# CPU.net
KiCad netlist of a schematic drawn in Altium Designer
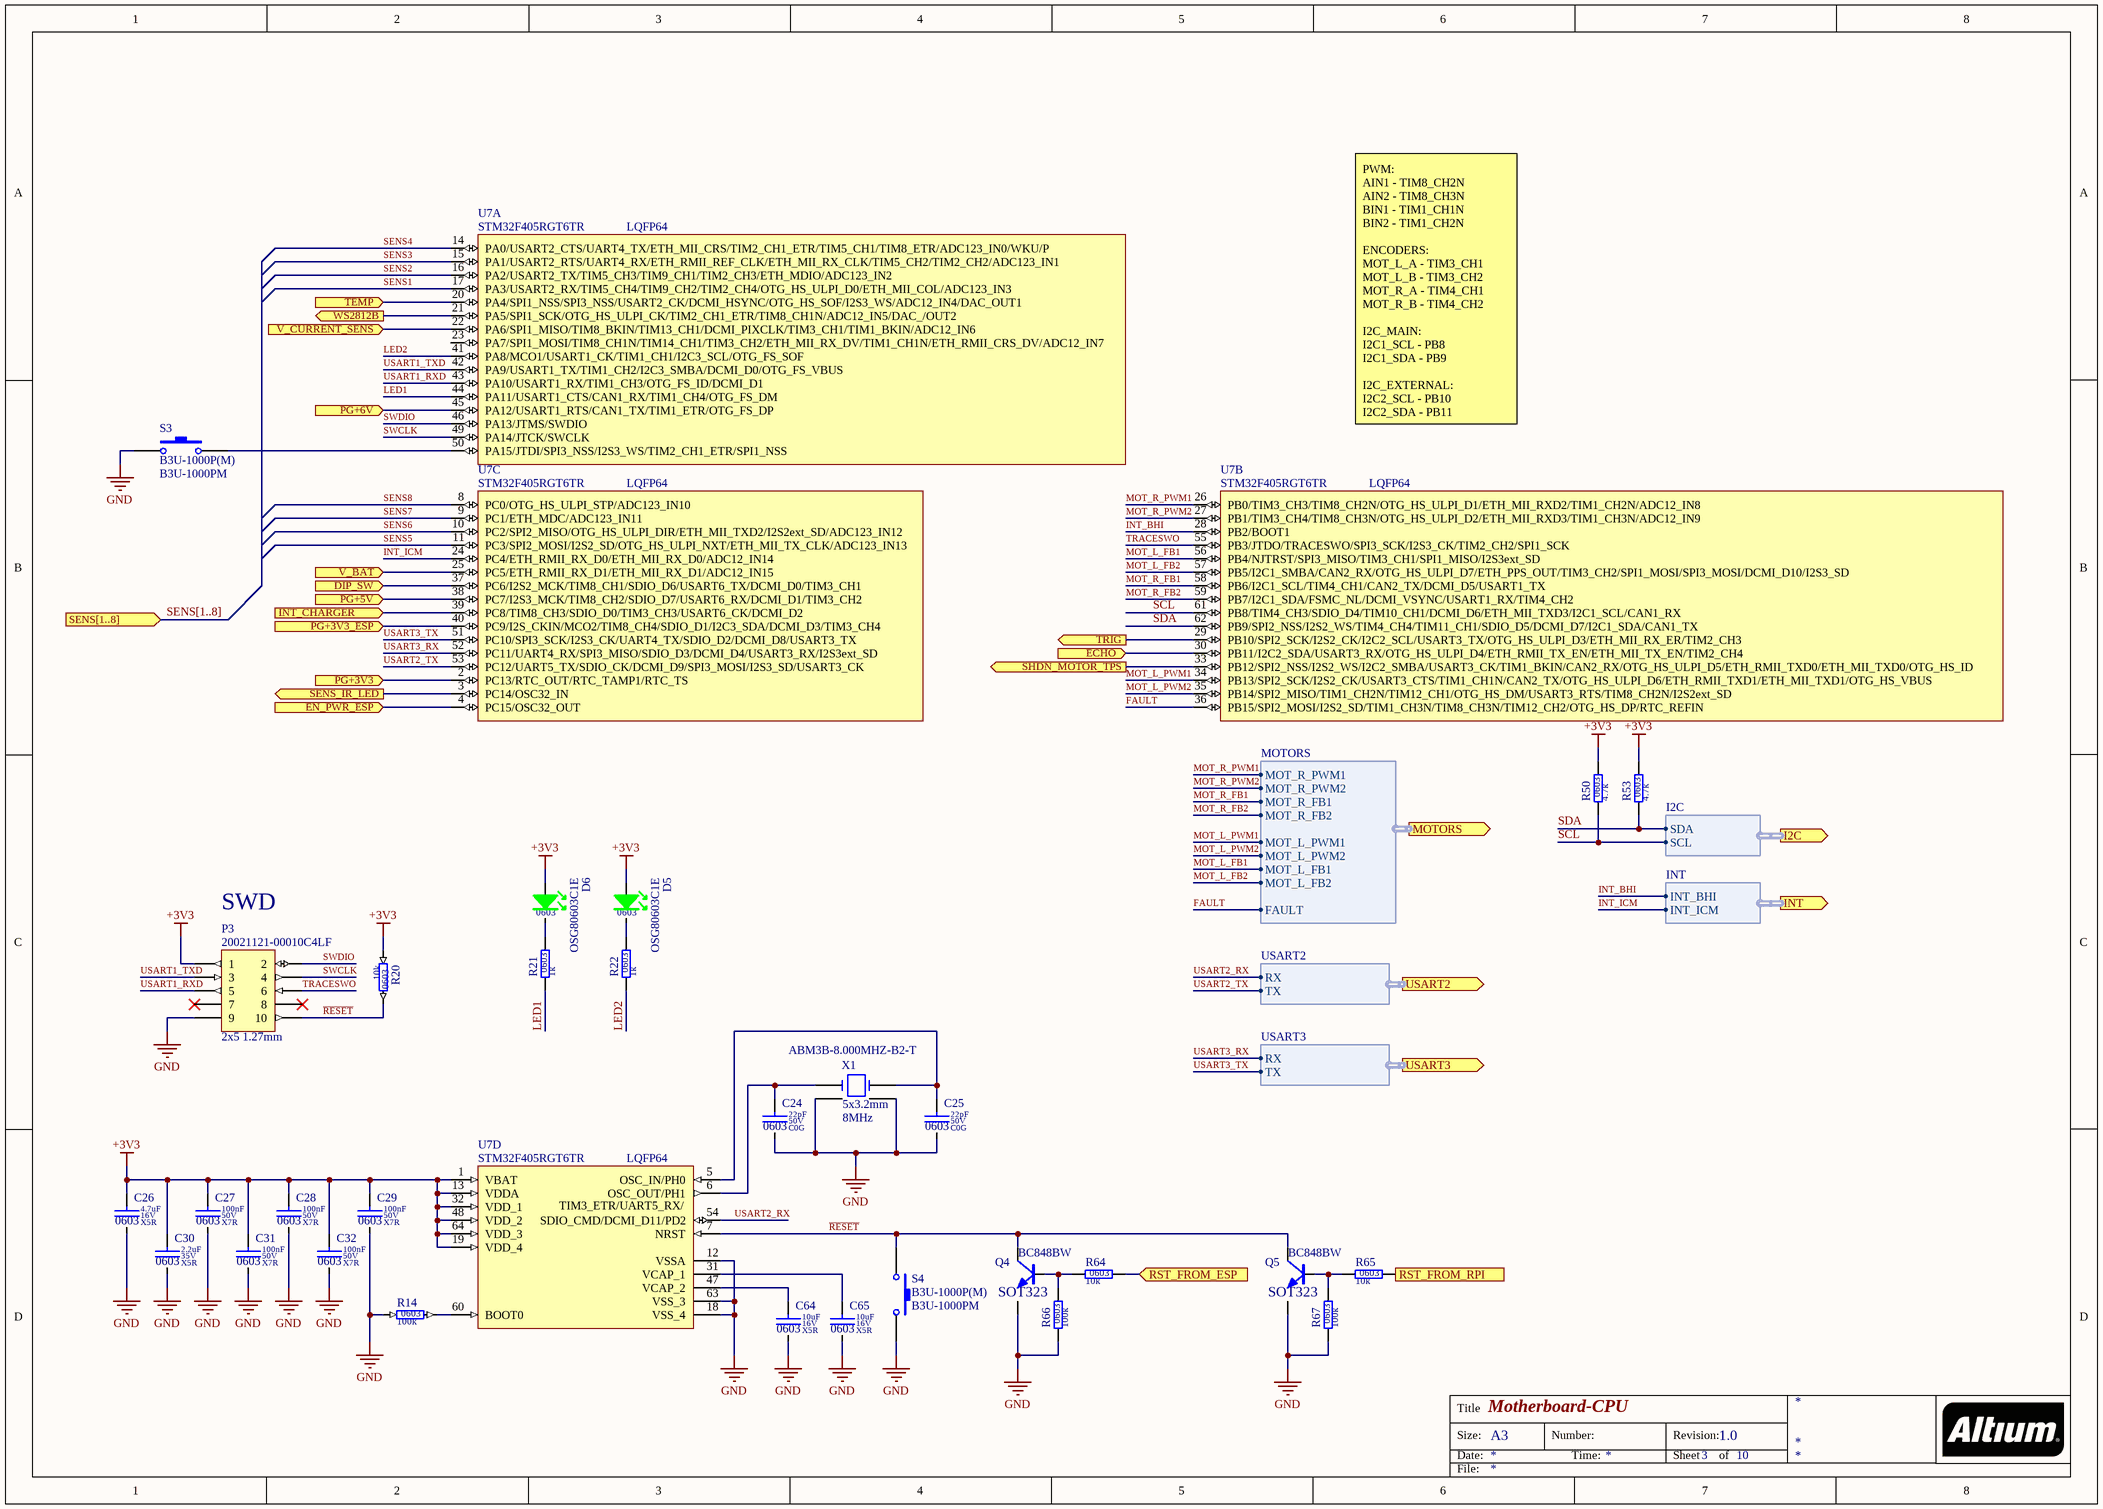
[diagram p0: CPU.SchDoc]

(export (version "E")
  (design (tool "Eeschema 10.0.6"))
  (components
    (comp (ref "C24")
      (value "22pF")
      (footprint "C_0603_1608")
      (description "Capacitor")
      (fields
        (field (name "DIELECTRIC") "C0G")
        (field (name "VOLTAGE") "50V")
        (field (name "SCH_FOOTPRINT") "0603")
        (field (name "PART NUMBER") "C_22pF_50V_C0G_0603_5")
        (field (name "MANUFACTURER") "Yageo")
      )
      (libsource (lib "Library") (part "C"))
    )
    (comp (ref "C25")
      (value "22pF")
      (footprint "C_0603_1608")
      (description "Capacitor")
      (fields
        (field (name "DIELECTRIC") "C0G")
        (field (name "VOLTAGE") "50V")
        (field (name "SCH_FOOTPRINT") "0603")
        (field (name "PART NUMBER") "C_22pF_50V_C0G_0603_5")
        (field (name "MANUFACTURER") "Yageo")
      )
      (libsource (lib "Library") (part "C"))
    )
    (comp (ref "C26")
      (value "4.7uF")
      (footprint "C_0603_1608")
      (description "Capacitor")
      (fields
        (field (name "DIELECTRIC") "X5R")
        (field (name "VOLTAGE") "16V")
        (field (name "SCH_FOOTPRINT") "0603")
        (field (name "PART NUMBER") "C_4.7uF_16V_X5R_0603_10")
        (field (name "MANUFACTURER") "Murata")
      )
      (libsource (lib "Library") (part "C"))
    )
    (comp (ref "C27")
      (value "100nF")
      (footprint "C_0603_1608")
      (description "Capacitor")
      (fields
        (field (name "DIELECTRIC") "X7R")
        (field (name "VOLTAGE") "50V")
        (field (name "SCH_FOOTPRINT") "0603")
        (field (name "PART NUMBER") "C_100nF_50V_X7R_0603_5")
        (field (name "MANUFACTURER") "Samsung")
      )
      (libsource (lib "Library") (part "C"))
    )
    (comp (ref "C28")
      (value "100nF")
      (footprint "C_0603_1608")
      (description "Capacitor")
      (fields
        (field (name "DIELECTRIC") "X7R")
        (field (name "VOLTAGE") "50V")
        (field (name "SCH_FOOTPRINT") "0603")
        (field (name "PART NUMBER") "C_100nF_50V_X7R_0603_5")
        (field (name "MANUFACTURER") "Samsung")
      )
      (libsource (lib "Library") (part "C"))
    )
    (comp (ref "C29")
      (value "100nF")
      (footprint "C_0603_1608")
      (description "Capacitor")
      (fields
        (field (name "DIELECTRIC") "X7R")
        (field (name "VOLTAGE") "50V")
        (field (name "SCH_FOOTPRINT") "0603")
        (field (name "PART NUMBER") "C_100nF_50V_X7R_0603_5")
        (field (name "MANUFACTURER") "Samsung")
      )
      (libsource (lib "Library") (part "C"))
    )
    (comp (ref "C30")
      (value "2.2uF")
      (footprint "C_0603_1608")
      (description "Capacitor")
      (fields
        (field (name "DIELECTRIC") "X5R")
        (field (name "VOLTAGE") "35V")
        (field (name "SCH_FOOTPRINT") "0603")
        (field (name "PART NUMBER") "C_2.2uF_35V_X5R_0603_10")
        (field (name "MANUFACTURER") "Murata")
      )
      (libsource (lib "Library") (part "C"))
    )
    (comp (ref "C31")
      (value "100nF")
      (footprint "C_0603_1608")
      (description "Capacitor")
      (fields
        (field (name "DIELECTRIC") "X7R")
        (field (name "VOLTAGE") "50V")
        (field (name "SCH_FOOTPRINT") "0603")
        (field (name "PART NUMBER") "C_100nF_50V_X7R_0603_5")
        (field (name "MANUFACTURER") "Samsung")
      )
      (libsource (lib "Library") (part "C"))
    )
    (comp (ref "C32")
      (value "100nF")
      (footprint "C_0603_1608")
      (description "Capacitor")
      (fields
        (field (name "DIELECTRIC") "X7R")
        (field (name "VOLTAGE") "50V")
        (field (name "SCH_FOOTPRINT") "0603")
        (field (name "PART NUMBER") "C_100nF_50V_X7R_0603_5")
        (field (name "MANUFACTURER") "Samsung")
      )
      (libsource (lib "Library") (part "C"))
    )
    (comp (ref "C64")
      (value "10uF")
      (footprint "C_0603_1608")
      (description "Capacitor")
      (fields
        (field (name "DIELECTRIC") "X5R")
        (field (name "VOLTAGE") "16V")
        (field (name "SCH_FOOTPRINT") "0603")
        (field (name "PART NUMBER") "C_10uF_16V_X5R_0603_20")
        (field (name "MANUFACTURER") "Samsung Electro-Mechanics")
      )
      (libsource (lib "Library") (part "C"))
    )
    (comp (ref "C65")
      (value "10uF")
      (footprint "C_0603_1608")
      (description "Capacitor")
      (fields
        (field (name "DIELECTRIC") "X5R")
        (field (name "VOLTAGE") "16V")
        (field (name "SCH_FOOTPRINT") "0603")
        (field (name "PART NUMBER") "C_10uF_16V_X5R_0603_20")
        (field (name "MANUFACTURER") "Samsung Electro-Mechanics")
      )
      (libsource (lib "Library") (part "C"))
    )
    (comp (ref "D5")
      (value "OSG80603C1E")
      (footprint "OL_0603_1608")
      (description "LED GREEN")
      (fields
        (field (name "SCH_FOOTPRINT") "0603")
        (field (name "PART NUMBER") "OL_G_0603_OSG80603C1E")
        (field (name "MANUFACTURER") "Optosupply")
      )
      (libsource (lib "Library") (part "OL_G"))
    )
    (comp (ref "D6")
      (value "OSG80603C1E")
      (footprint "OL_0603_1608")
      (description "LED GREEN")
      (fields
        (field (name "SCH_FOOTPRINT") "0603")
        (field (name "PART NUMBER") "OL_G_0603_OSG80603C1E")
        (field (name "MANUFACTURER") "Optosupply")
      )
      (libsource (lib "Library") (part "OL_G"))
    )
    (comp (ref "P3")
      (value "20021121-00010C4LF")
      (footprint "P_HEADER_2x5_1.27")
      (description "Pin Header")
      (fields
        (field (name "PART NUMBER") "P_HEADER_2x5_1.27")
        (field (name "SCH_FOOTPRINT") "2x5 1.27mm")
        (field (name "MANUFACTURER") "FCI")
      )
      (libsource (lib "Library") (part "P_HEADER_2x5"))
    )
    (comp (ref "Q4")
      (value "BC848BW")
      (footprint "SOT323_SC70")
      (fields
        (field (name "PART NUMBER") "QNP_BC848BW_30V_0A1")
        (field (name "SCH_FOOTPRINT") "SOT323")
        (field (name "VOLTAGE") "30V")
        (field (name "MANUFACTURER") "Diotec Semiconductor")
      )
      (libsource (lib "Library") (part "QNP_BEC"))
    )
    (comp (ref "Q5")
      (value "BC848BW")
      (footprint "SOT323_SC70")
      (fields
        (field (name "PART NUMBER") "QNP_BC848BW_30V_0A1")
        (field (name "SCH_FOOTPRINT") "SOT323")
        (field (name "VOLTAGE") "30V")
        (field (name "MANUFACTURER") "Diotec Semiconductor")
      )
      (libsource (lib "Library") (part "QNP_BEC"))
    )
    (comp (ref "R14")
      (value "100k")
      (footprint "R_0603_1608")
      (fields
        (field (name "SCH_FOOTPRINT") "0603")
        (field (name "PART NUMBER") "R_100k_0603_1")
        (field (name "VOLTAGE") "50V")
        (field (name "POWER") "100mW")
      )
      (libsource (lib "") (part "R_1"))
    )
    (comp (ref "R20")
      (value "10k")
      (footprint "R_0603_1608")
      (fields
        (field (name "SCH_FOOTPRINT") "0603")
        (field (name "PART NUMBER") "R_10k_0603_1")
        (field (name "VOLTAGE") "75V")
        (field (name "POWER") "100mW")
      )
      (libsource (lib "") (part "R_1"))
    )
    (comp (ref "R21")
      (value "1k")
      (footprint "R_0603_1608")
      (fields
        (field (name "SCH_FOOTPRINT") "0603")
        (field (name "PART NUMBER") "R_1k_0603_1")
        (field (name "VOLTAGE") "75V")
        (field (name "POWER") "100mW")
      )
      (libsource (lib "Library") (part "R"))
    )
    (comp (ref "R22")
      (value "1k")
      (footprint "R_0603_1608")
      (fields
        (field (name "SCH_FOOTPRINT") "0603")
        (field (name "PART NUMBER") "R_1k_0603_1")
        (field (name "VOLTAGE") "75V")
        (field (name "POWER") "100mW")
      )
      (libsource (lib "Library") (part "R"))
    )
    (comp (ref "R50")
      (value "4.7k")
      (footprint "R_0603_1608")
      (fields
        (field (name "SCH_FOOTPRINT") "0603")
        (field (name "PART NUMBER") "R_4.7k_0603_1")
        (field (name "VOLTAGE") "75V")
        (field (name "POWER") "100mW")
      )
      (libsource (lib "Library") (part "R"))
    )
    (comp (ref "R53")
      (value "4.7k")
      (footprint "R_0603_1608")
      (fields
        (field (name "SCH_FOOTPRINT") "0603")
        (field (name "PART NUMBER") "R_4.7k_0603_1")
        (field (name "VOLTAGE") "75V")
        (field (name "POWER") "100mW")
      )
      (libsource (lib "Library") (part "R"))
    )
    (comp (ref "R64")
      (value "10k")
      (footprint "R_0603_1608")
      (fields
        (field (name "SCH_FOOTPRINT") "0603")
        (field (name "PART NUMBER") "R_10k_0603_1")
        (field (name "VOLTAGE") "75V")
        (field (name "POWER") "100mW")
      )
      (libsource (lib "Library") (part "R"))
    )
    (comp (ref "R65")
      (value "10k")
      (footprint "R_0603_1608")
      (fields
        (field (name "SCH_FOOTPRINT") "0603")
        (field (name "PART NUMBER") "R_10k_0603_1")
        (field (name "VOLTAGE") "75V")
        (field (name "POWER") "100mW")
      )
      (libsource (lib "Library") (part "R"))
    )
    (comp (ref "R66")
      (value "100k")
      (footprint "R_0603_1608")
      (fields
        (field (name "SCH_FOOTPRINT") "0603")
        (field (name "PART NUMBER") "R_100k_0603_1")
        (field (name "VOLTAGE") "50V")
        (field (name "POWER") "100mW")
      )
      (libsource (lib "Library") (part "R"))
    )
    (comp (ref "R67")
      (value "100k")
      (footprint "R_0603_1608")
      (fields
        (field (name "SCH_FOOTPRINT") "0603")
        (field (name "PART NUMBER") "R_100k_0603_1")
        (field (name "VOLTAGE") "50V")
        (field (name "POWER") "100mW")
      )
      (libsource (lib "Library") (part "R"))
    )
    (comp (ref "S3")
      (value "B3U-1000PM")
      (footprint "B3U-1000P")
      (description "Tact Switch")
      (fields
        (field (name "PART NUMBER") "S_B3U-1000PM")
        (field (name "SCH_FOOTPRINT") "B3U-1000P(M)")
        (field (name "MANUFACTURER") "OMRON")
      )
      (libsource (lib "Library") (part "S_TACTSWITCH"))
    )
    (comp (ref "S4")
      (value "B3U-1000PM")
      (footprint "B3U-1000P")
      (description "Tact Switch")
      (fields
        (field (name "PART NUMBER") "S_B3U-1000PM")
        (field (name "SCH_FOOTPRINT") "B3U-1000P(M)")
        (field (name "MANUFACTURER") "OMRON")
      )
      (libsource (lib "Library") (part "S_TACTSWITCH"))
    )
    (comp (ref "U7")
      (value "STM32F405RGT6TR")
      (footprint "LQFP64_10x10")
      (fields
        (field (name "SCH_FOOTPRINT") "LQFP64")
        (field (name "PART NUMBER") "UP_STM32F405RGT6TR")
        (field (name "MANUFACTURER") "STMicroelectronics")
        (field (name "Comment") "STM32F405RBT6")
      )
      (libsource (lib "Library") (part "UP_STM32F405Rx"))
    )
    (comp (ref "X1")
      (value "8MHz")
      (footprint "X_ABM3B_5X3X11")
      (fields
        (field (name "PART NUMBER") "X_ABM3B-8.000MHZ-B2-T")
        (field (name "MANUFACTURER PART NUMBER") "ABM3B-8.000MHZ-B2-T")
        (field (name "SCH_FOOTPRINT") "5x3.2mm")
        (field (name "MANUFACTURER") "Abracon")
      )
      (libsource (lib "Library") (part "X_ABM3B"))
    )
  )
  (nets
    (net (code "6") (name "+3V3") (class "Default")
      (node (ref "C26") (pin "1") (pinfunction "1_1") (pintype "passive"))
      (node (ref "C27") (pin "1") (pinfunction "1_1") (pintype "passive"))
      (node (ref "C28") (pin "1") (pinfunction "1_1") (pintype "passive"))
      (node (ref "C29") (pin "1") (pinfunction "1_1") (pintype "passive"))
      (node (ref "C30") (pin "1") (pinfunction "1_1") (pintype "passive"))
      (node (ref "C31") (pin "1") (pinfunction "1_1") (pintype "passive"))
      (node (ref "C32") (pin "1") (pinfunction "1_1") (pintype "passive"))
      (node (ref "D5") (pin "2") (pinfunction "A_2") (pintype "passive"))
      (node (ref "D6") (pin "2") (pinfunction "A_2") (pintype "passive"))
      (node (ref "P3") (pin "1") (pinfunction "1_1") (pintype "output"))
      (node (ref "R20") (pin "1") (pinfunction "1_1") (pintype "input"))
      (node (ref "R50") (pin "2") (pinfunction "2_2") (pintype "passive"))
      (node (ref "R53") (pin "2") (pinfunction "2_2") (pintype "passive"))
      (node (ref "U7") (pin "1") (pinfunction "VBAT_1") (pintype "input"))
      (node (ref "U7") (pin "13") (pinfunction "VDDA_13") (pintype "input"))
      (node (ref "U7") (pin "19") (pinfunction "VDD_4_19") (pintype "input"))
      (node (ref "U7") (pin "32") (pinfunction "VDD_1_32") (pintype "input"))
      (node (ref "U7") (pin "48") (pinfunction "VDD_2_48") (pintype "input"))
      (node (ref "U7") (pin "64") (pinfunction "VDD_3_64") (pintype "input"))
    )
    (net (code "7") (name "/DIP_SW") (class "Default")
      (node (ref "U7") (pin "37") (pinfunction "PC6/I2S2_MCK/TIM8_CH1/SDIO_D6/USART6_TX/DCMI_D0/TIM3_CH1_37") (pintype "bidirectional"))
    )
    (net (code "8") (name "/ECHO") (class "Default")
      (node (ref "U7") (pin "30") (pinfunction "PB11/I2C2_SDA/USART3_RX/OTG_HS_ULPI_D4/ETH_RMII_TX_EN/ETH_MII_TX_EN/TIM2_CH4_30") (pintype "bidirectional"))
    )
    (net (code "9") (name "/EN_PWR_ESP") (class "Default")
      (node (ref "U7") (pin "4") (pinfunction "PC15/OSC32_OUT_4") (pintype "bidirectional"))
    )
    (net (code "10") (name "/FAULT") (class "Default")
      (node (ref "U7") (pin "36") (pinfunction "PB15/SPI2_MOSI/I2S2_SD/TIM1_CH3N/TIM8_CH3N/TIM12_CH2/OTG_HS_DP/RTC_REFIN_36") (pintype "bidirectional"))
    )
    (net (code "11") (name "/INT_BHI") (class "Default")
      (node (ref "U7") (pin "28") (pinfunction "PB2/BOOT1_28") (pintype "bidirectional"))
    )
    (net (code "12") (name "/INT_CHARGER") (class "Default")
      (node (ref "U7") (pin "39") (pinfunction "PC8/TIM8_CH3/SDIO_D0/TIM3_CH3/USART6_CK/DCMI_D2_39") (pintype "bidirectional"))
    )
    (net (code "13") (name "/INT_ICM") (class "Default")
      (node (ref "U7") (pin "24") (pinfunction "PC4/ETH_RMII_RX_D0/ETH_MII_RX_D0/ADC12_IN14_24") (pintype "bidirectional"))
    )
    (net (code "14") (name "/LED1") (class "Default")
      (node (ref "R21") (pin "1") (pinfunction "1_1") (pintype "passive"))
      (node (ref "U7") (pin "44") (pinfunction "PA11/USART1_CTS/CAN1_RX/TIM1_CH4/OTG_FS_DM_44") (pintype "bidirectional"))
    )
    (net (code "15") (name "/LED2") (class "Default")
      (node (ref "R22") (pin "1") (pinfunction "1_1") (pintype "passive"))
      (node (ref "U7") (pin "41") (pinfunction "PA8/MCO1/USART1_CK/TIM1_CH1/I2C3_SCL/OTG_FS_SOF_41") (pintype "bidirectional"))
    )
    (net (code "16") (name "/MOT_L_FB1") (class "Default")
      (node (ref "U7") (pin "56") (pinfunction "PB4/NJTRST/SPI3_MISO/TIM3_CH1/SPI1_MISO/I2S3ext_SD_56") (pintype "bidirectional"))
    )
    (net (code "17") (name "/MOT_L_FB2") (class "Default")
      (node (ref "U7") (pin "57") (pinfunction "PB5/I2C1_SMBA/CAN2_RX/OTG_HS_ULPI_D7/ETH_PPS_OUT/TIM3_CH2/SPI1_MOSI/SPI3_MOSI/DCMI_D10/I2S3_SD_57") (pintype "bidirectional"))
    )
    (net (code "18") (name "/MOT_L_PWM1") (class "Default")
      (node (ref "U7") (pin "34") (pinfunction "PB13/SPI2_SCK/I2S2_CK/USART3_CTS/TIM1_CH1N/CAN2_TX/OTG_HS_ULPI_D6/ETH_RMII_TXD1/ETH_MII_TXD1/OTG_HS_VBUS_34") (pintype "bidirectional"))
    )
    (net (code "19") (name "/MOT_L_PWM2") (class "Default")
      (node (ref "U7") (pin "35") (pinfunction "PB14/SPI2_MISO/TIM1_CH2N/TIM12_CH1/OTG_HS_DM/USART3_RTS/TIM8_CH2N/I2S2ext_SD_35") (pintype "bidirectional"))
    )
    (net (code "20") (name "/MOT_R_FB1") (class "Default")
      (node (ref "U7") (pin "58") (pinfunction "PB6/I2C1_SCL/TIM4_CH1/CAN2_TX/DCMI_D5/USART1_TX_58") (pintype "bidirectional"))
    )
    (net (code "21") (name "/MOT_R_FB2") (class "Default")
      (node (ref "U7") (pin "59") (pinfunction "PB7/I2C1_SDA/FSMC_NL/DCMI_VSYNC/USART1_RX/TIM4_CH2_59") (pintype "bidirectional"))
    )
    (net (code "22") (name "/MOT_R_PWM1") (class "Default")
      (node (ref "U7") (pin "26") (pinfunction "PB0/TIM3_CH3/TIM8_CH2N/OTG_HS_ULPI_D1/ETH_MII_RXD2/TIM1_CH2N/ADC12_IN8_26") (pintype "bidirectional"))
    )
    (net (code "23") (name "/MOT_R_PWM2") (class "Default")
      (node (ref "U7") (pin "27") (pinfunction "PB1/TIM3_CH4/TIM8_CH3N/OTG_HS_ULPI_D2/ETH_MII_RXD3/TIM1_CH3N/ADC12_IN9_27") (pintype "bidirectional"))
    )
    (net (code "24") (name "/PG+3V3") (class "Default")
      (node (ref "U7") (pin "2") (pinfunction "PC13/RTC_OUT/RTC_TAMP1/RTC_TS_2") (pintype "bidirectional"))
    )
    (net (code "25") (name "/PG+3V3_ESP") (class "Default")
      (node (ref "U7") (pin "40") (pinfunction "PC9/I2S_CKIN/MCO2/TIM8_CH4/SDIO_D1/I2C3_SDA/DCMI_D3/TIM3_CH4_40") (pintype "bidirectional"))
    )
    (net (code "26") (name "/PG+5V") (class "Default")
      (node (ref "U7") (pin "38") (pinfunction "PC7/I2S3_MCK/TIM8_CH2/SDIO_D7/USART6_RX/DCMI_D1/TIM3_CH2_38") (pintype "bidirectional"))
    )
    (net (code "27") (name "/PG+6V") (class "Default")
      (node (ref "U7") (pin "45") (pinfunction "PA12/USART1_RTS/CAN1_TX/TIM1_ETR/OTG_FS_DP_45") (pintype "bidirectional"))
    )
    (net (code "28") (name "/RST_FROM_ESP") (class "Default")
      (node (ref "R64") (pin "2") (pinfunction "2_2") (pintype "passive"))
    )
    (net (code "29") (name "/RST_FROM_RPI") (class "Default")
      (node (ref "R65") (pin "2") (pinfunction "2_2") (pintype "passive"))
    )
    (net (code "30") (name "/SCL") (class "Default")
      (node (ref "R50") (pin "1") (pinfunction "1_1") (pintype "passive"))
      (node (ref "U7") (pin "61") (pinfunction "PB8/TIM4_CH3/SDIO_D4/TIM10_CH1/DCMI_D6/ETH_MII_TXD3/I2C1_SCL/CAN1_RX_61") (pintype "bidirectional"))
    )
    (net (code "31") (name "/SDA") (class "Default")
      (node (ref "R53") (pin "1") (pinfunction "1_1") (pintype "passive"))
      (node (ref "U7") (pin "62") (pinfunction "PB9/SPI2_NSS/I2S2_WS/TIM4_CH4/TIM11_CH1/SDIO_D5/DCMI_D7/I2C1_SDA/CAN1_TX_62") (pintype "bidirectional"))
    )
    (net (code "32") (name "/SENS1") (class "Default")
      (node (ref "U7") (pin "17") (pinfunction "PA3/USART2_RX/TIM5_CH4/TIM9_CH2/TIM2_CH4/OTG_HS_ULPI_D0/ETH_MII_COL/ADC123_IN3_17") (pintype "bidirectional"))
    )
    (net (code "33") (name "/SENS2") (class "Default")
      (node (ref "U7") (pin "16") (pinfunction "PA2/USART2_TX/TIM5_CH3/TIM9_CH1/TIM2_CH3/ETH_MDIO/ADC123_IN2_16") (pintype "bidirectional"))
    )
    (net (code "34") (name "/SENS3") (class "Default")
      (node (ref "U7") (pin "15") (pinfunction "PA1/USART2_RTS/UART4_RX/ETH_RMII_REF_CLK/ETH_MII_RX_CLK/TIM5_CH2/TIM2_CH2/ADC123_IN1_15") (pintype "bidirectional"))
    )
    (net (code "35") (name "/SENS4") (class "Default")
      (node (ref "U7") (pin "14") (pinfunction "PA0/USART2_CTS/UART4_TX/ETH_MII_CRS/TIM2_CH1_ETR/TIM5_CH1/TIM8_ETR/ADC123_IN0/WKU/P_14") (pintype "bidirectional"))
    )
    (net (code "36") (name "/SENS5") (class "Default")
      (node (ref "U7") (pin "11") (pinfunction "PC3/SPI2_MOSI/I2S2_SD/OTG_HS_ULPI_NXT/ETH_MII_TX_CLK/ADC123_IN13_11") (pintype "bidirectional"))
    )
    (net (code "37") (name "/SENS6") (class "Default")
      (node (ref "U7") (pin "10") (pinfunction "PC2/SPI2_MISO/OTG_HS_ULPI_DIR/ETH_MII_TXD2/I2S2ext_SD/ADC123_IN12_10") (pintype "bidirectional"))
    )
    (net (code "38") (name "/SENS7") (class "Default")
      (node (ref "U7") (pin "9") (pinfunction "PC1/ETH_MDC/ADC123_IN11_9") (pintype "bidirectional"))
    )
    (net (code "39") (name "/SENS8") (class "Default")
      (node (ref "U7") (pin "8") (pinfunction "PC0/OTG_HS_ULPI_STP/ADC123_IN10_8") (pintype "bidirectional"))
    )
    (net (code "41") (name "/SENS_IR_LED") (class "Default")
      (node (ref "U7") (pin "3") (pinfunction "PC14/OSC32_IN_3") (pintype "bidirectional"))
    )
    (net (code "42") (name "/SHDN_MOTOR_TPS") (class "Default")
      (node (ref "U7") (pin "33") (pinfunction "PB12/SPI2_NSS/I2S2_WS/I2C2_SMBA/USART3_CK/TIM1_BKIN/CAN2_RX/OTG_HS_ULPI_D5/ETH_RMII_TXD0/ETH_MII_TXD0/OTG_HS_ID_33") (pintype "bidirectional"))
    )
    (net (code "43") (name "/SWCLK") (class "Default")
      (node (ref "P3") (pin "4") (pinfunction "4_4") (pintype "output"))
      (node (ref "U7") (pin "49") (pinfunction "PA14/JTCK/SWCLK_49") (pintype "bidirectional"))
    )
    (net (code "44") (name "/SWDIO") (class "Default")
      (node (ref "P3") (pin "2") (pinfunction "2_2") (pintype "bidirectional"))
      (node (ref "U7") (pin "46") (pinfunction "PA13/JTMS/SWDIO_46") (pintype "bidirectional"))
    )
    (net (code "45") (name "/TEMP") (class "Default")
      (node (ref "U7") (pin "20") (pinfunction "PA4/SPI1_NSS/SPI3_NSS/USART2_CK/DCMI_HSYNC/OTG_HS_SOF/I2S3_WS/ADC12_IN4/DAC_OUT1_20") (pintype "bidirectional"))
    )
    (net (code "46") (name "/TRACESWO") (class "Default")
      (node (ref "P3") (pin "6") (pinfunction "6_6") (pintype "input"))
      (node (ref "U7") (pin "55") (pinfunction "PB3/JTDO/TRACESWO/SPI3_SCK/I2S3_CK/TIM2_CH2/SPI1_SCK_55") (pintype "bidirectional"))
    )
    (net (code "47") (name "/TRIG") (class "Default")
      (node (ref "U7") (pin "29") (pinfunction "PB10/SPI2_SCK/I2S2_CK/I2C2_SCL/USART3_TX/OTG_HS_ULPI_D3/ETH_MII_RX_ER/TIM2_CH3_29") (pintype "bidirectional"))
    )
    (net (code "48") (name "/USART1_RXD") (class "Default")
      (node (ref "P3") (pin "5") (pinfunction "5_5") (pintype "output"))
      (node (ref "U7") (pin "43") (pinfunction "PA10/USART1_RX/TIM1_CH3/OTG_FS_ID/DCMI_D1_43") (pintype "bidirectional"))
    )
    (net (code "49") (name "/USART1_TXD") (class "Default")
      (node (ref "P3") (pin "3") (pinfunction "3_3") (pintype "input"))
      (node (ref "U7") (pin "42") (pinfunction "PA9/USART1_TX/TIM1_CH2/I2C3_SMBA/DCMI_D0/OTG_FS_VBUS_42") (pintype "bidirectional"))
    )
    (net (code "50") (name "/USART2_RX") (class "Default")
      (node (ref "U7") (pin "54") (pinfunction "SDIO_CMD/DCMI_D11/PD2_54") (pintype "bidirectional"))
    )
    (net (code "51") (name "/USART2_TX") (class "Default")
      (node (ref "U7") (pin "53") (pinfunction "PC12/UART5_TX/SDIO_CK/DCMI_D9/SPI3_MOSI/I2S3_SD/USART3_CK_53") (pintype "bidirectional"))
    )
    (net (code "52") (name "/USART3_RX") (class "Default")
      (node (ref "U7") (pin "52") (pinfunction "PC11/UART4_RX/SPI3_MISO/SDIO_D3/DCMI_D4/USART3_RX/I2S3ext_SD_52") (pintype "bidirectional"))
    )
    (net (code "53") (name "/USART3_TX") (class "Default")
      (node (ref "U7") (pin "51") (pinfunction "PC10/SPI3_SCK/I2S3_CK/UART4_TX/SDIO_D2/DCMI_D8/USART3_TX_51") (pintype "bidirectional"))
    )
    (net (code "54") (name "/V_BAT") (class "Default")
      (node (ref "U7") (pin "25") (pinfunction "PC5/ETH_RMII_RX_D1/ETH_MII_RX_D1/ADC12_IN15_25") (pintype "bidirectional"))
    )
    (net (code "55") (name "/V_CURRENT_SENS") (class "Default")
      (node (ref "U7") (pin "22") (pinfunction "PA6/SPI1_MISO/TIM8_BKIN/TIM13_CH1/DCMI_PIXCLK/TIM3_CH1/TIM1_BKIN/ADC12_IN6_22") (pintype "bidirectional"))
    )
    (net (code "56") (name "/WS2812B") (class "Default")
      (node (ref "U7") (pin "21") (pinfunction "PA5/SPI1_SCK/OTG_HS_ULPI_CK/TIM2_CH1_ETR/TIM8_CH1N/ADC12_IN5/DAC_/OUT2_21") (pintype "bidirectional"))
    )
    (net (code "62") (name "/~{RESET}") (class "Default")
      (node (ref "P3") (pin "10") (pinfunction "10_10") (pintype "output"))
      (node (ref "Q4") (pin "3") (pinfunction "C_3") (pintype "passive"))
      (node (ref "Q5") (pin "3") (pinfunction "C_3") (pintype "passive"))
      (node (ref "R20") (pin "2") (pinfunction "2_2") (pintype "output"))
      (node (ref "S4") (pin "1") (pinfunction "1_1") (pintype "passive"))
      (node (ref "U7") (pin "7") (pinfunction "NRST_7") (pintype "input"))
    )
    (net (code "63") (name "GND") (class "Default")
      (node (ref "C24") (pin "2") (pinfunction "2_2") (pintype "passive"))
      (node (ref "C25") (pin "2") (pinfunction "2_2") (pintype "passive"))
      (node (ref "C26") (pin "2") (pinfunction "2_2") (pintype "passive"))
      (node (ref "C27") (pin "2") (pinfunction "2_2") (pintype "passive"))
      (node (ref "C28") (pin "2") (pinfunction "2_2") (pintype "passive"))
      (node (ref "C29") (pin "2") (pinfunction "2_2") (pintype "passive"))
      (node (ref "C30") (pin "2") (pinfunction "2_2") (pintype "passive"))
      (node (ref "C31") (pin "2") (pinfunction "2_2") (pintype "passive"))
      (node (ref "C32") (pin "2") (pinfunction "2_2") (pintype "passive"))
      (node (ref "C64") (pin "2") (pinfunction "2_2") (pintype "passive"))
      (node (ref "C65") (pin "2") (pinfunction "2_2") (pintype "passive"))
      (node (ref "P3") (pin "9") (pinfunction "9_9") (pintype "passive"))
      (node (ref "Q4") (pin "2") (pinfunction "E_2") (pintype "passive"))
      (node (ref "Q5") (pin "2") (pinfunction "E_2") (pintype "passive"))
      (node (ref "R14") (pin "1") (pinfunction "1_1") (pintype "input"))
      (node (ref "R66") (pin "1") (pinfunction "1_1") (pintype "passive"))
      (node (ref "R67") (pin "1") (pinfunction "1_1") (pintype "passive"))
      (node (ref "S3") (pin "1") (pinfunction "1_1") (pintype "passive"))
      (node (ref "S4") (pin "2") (pinfunction "2_2") (pintype "passive"))
      (node (ref "U7") (pin "12") (pinfunction "VSSA_12") (pintype "power_in"))
      (node (ref "U7") (pin "18") (pinfunction "VSS_4_18") (pintype "power_in"))
      (node (ref "U7") (pin "63") (pinfunction "VSS_3_63") (pintype "power_in"))
      (node (ref "X1") (pin "2") (pinfunction "GND_2") (pintype "power_in"))
      (node (ref "X1") (pin "4") (pinfunction "GND_4") (pintype "power_in"))
    )
    (net (code "64") (name "Net-(D5-K)") (class "Default")
      (node (ref "D5") (pin "1") (pinfunction "K_1") (pintype "passive"))
      (node (ref "R22") (pin "2") (pinfunction "2_2") (pintype "passive"))
    )
    (net (code "65") (name "Net-(D6-K)") (class "Default")
      (node (ref "D6") (pin "1") (pinfunction "K_1") (pintype "passive"))
      (node (ref "R21") (pin "2") (pinfunction "2_2") (pintype "passive"))
    )
    (net (code "66") (name "Net-(Q4-B)") (class "Default")
      (node (ref "Q4") (pin "1") (pinfunction "B_1") (pintype "passive"))
      (node (ref "R64") (pin "1") (pinfunction "1_1") (pintype "passive"))
      (node (ref "R66") (pin "2") (pinfunction "2_2") (pintype "passive"))
    )
    (net (code "67") (name "Net-(Q5-B)") (class "Default")
      (node (ref "Q5") (pin "1") (pinfunction "B_1") (pintype "passive"))
      (node (ref "R65") (pin "1") (pinfunction "1_1") (pintype "passive"))
      (node (ref "R67") (pin "2") (pinfunction "2_2") (pintype "passive"))
    )
    (net (code "68") (name "Net-(U7A-PA15{slash}JTDI{slash}SPI3_NSS{slash}I2S3_WS{slash}TIM2_CH1_ETR{slash}SPI1_NSS)") (class "Default")
      (node (ref "S3") (pin "2") (pinfunction "2_2") (pintype "passive"))
      (node (ref "U7") (pin "50") (pinfunction "PA15/JTDI/SPI3_NSS/I2S3_WS/TIM2_CH1_ETR/SPI1_NSS_50") (pintype "bidirectional"))
    )
    (net (code "69") (name "Net-(U7D-BOOT0)") (class "Default")
      (node (ref "R14") (pin "2") (pinfunction "2_2") (pintype "output"))
      (node (ref "U7") (pin "60") (pinfunction "BOOT0_60") (pintype "input"))
    )
    (net (code "70") (name "Net-(U7D-OSC_IN{slash}PH0)") (class "Default")
      (node (ref "C25") (pin "1") (pinfunction "1_1") (pintype "passive"))
      (node (ref "U7") (pin "5") (pinfunction "OSC_IN/PH0_5") (pintype "input"))
      (node (ref "X1") (pin "1") (pinfunction "1_1") (pintype "passive"))
    )
    (net (code "71") (name "Net-(U7D-OSC_OUT{slash}PH1)") (class "Default")
      (node (ref "C24") (pin "1") (pinfunction "1_1") (pintype "passive"))
      (node (ref "U7") (pin "6") (pinfunction "OSC_OUT/PH1_6") (pintype "output"))
      (node (ref "X1") (pin "3") (pinfunction "3_3") (pintype "passive"))
    )
    (net (code "72") (name "Net-(U7D-VCAP_1)") (class "Default")
      (node (ref "C65") (pin "1") (pinfunction "1_1") (pintype "passive"))
      (node (ref "U7") (pin "31") (pinfunction "VCAP_1_31") (pintype "power_in"))
    )
    (net (code "73") (name "Net-(U7D-VCAP_2)") (class "Default")
      (node (ref "C64") (pin "1") (pinfunction "1_1") (pintype "passive"))
      (node (ref "U7") (pin "47") (pinfunction "VCAP_2_47") (pintype "power_in"))
    )
    (net (code "74") (name "unconnected-(P3-Pad7)") (class "Default")
      (node (ref "P3") (pin "7") (pinfunction "7_7") (pintype "passive+no_connect"))
    )
    (net (code "75") (name "unconnected-(P3-Pad8)") (class "Default")
      (node (ref "P3") (pin "8") (pinfunction "8_8") (pintype "passive+no_connect"))
    )
    (net (code "76") (name "unconnected-(U7A-PA7{slash}SPI1_MOSI{slash}TIM8_CH1N{slash}TIM14_CH1{slash}TIM3_CH2{slash}ETH_MII_RX_DV{slash}TIM1_CH1N{slash}ETH_RMII_CRS_DV{slash}ADC12_IN7-Pad23)") (class "Default")
      (node (ref "U7") (pin "23") (pinfunction "PA7/SPI1_MOSI/TIM8_CH1N/TIM14_CH1/TIM3_CH2/ETH_MII_RX_DV/TIM1_CH1N/ETH_RMII_CRS_DV/ADC12_IN7_23") (pintype "bidirectional"))
    )
  )
)
